# module_HC05.net
KiCad netlist of a schematic drawn in EAGLE
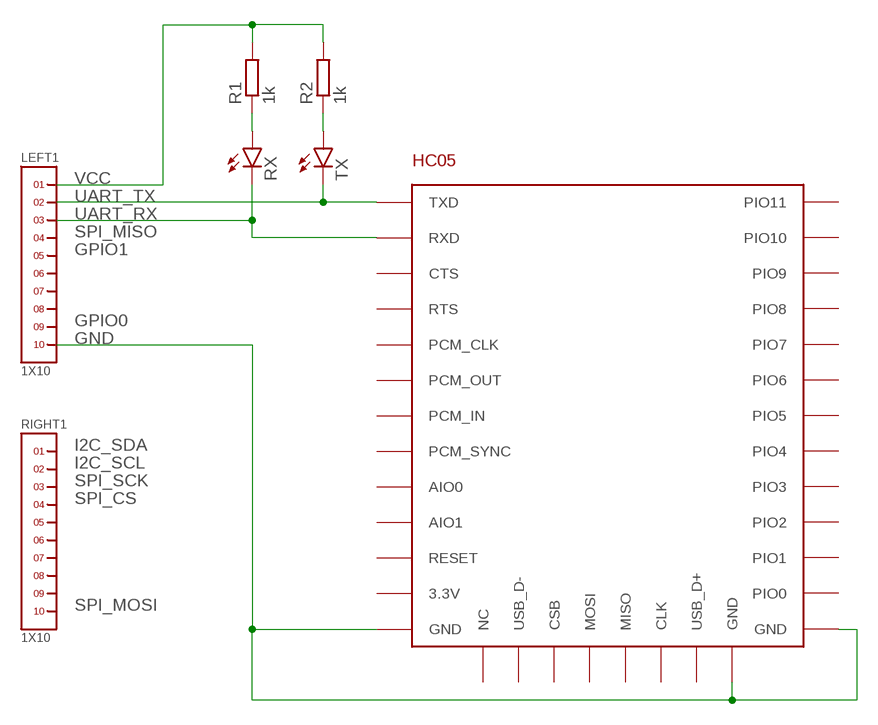
[diagram p0: schematic, sheet 1]

(export (version "E")
  (design (tool "Eeschema 10.0.6"))
  (components
    (comp (ref "LEFT1")
      (value "1X10")
      (footprint "eagle-import:1X10")
      (libsource (lib "eagle-import") (part "1X10"))
    )
    (comp (ref "R1")
      (value "1k")
      (footprint "eagle-import:R0603")
      (libsource (lib "eagle-import") (part "R-EU_R0603"))
    )
    (comp (ref "R2")
      (value "1k")
      (footprint "eagle-import:R0603")
      (libsource (lib "eagle-import") (part "R-EU_R0603"))
    )
    (comp (ref "RIGHT1")
      (value "1X10")
      (footprint "eagle-import:1X10")
      (libsource (lib "eagle-import") (part "1X10"))
    )
    (comp (ref "RX")
      (value "LEDCHIP-LED0603")
      (footprint "eagle-import:CHIP-LED0603")
      (libsource (lib "eagle-import") (part "LEDCHIP-LED0603"))
    )
    (comp (ref "TX")
      (value "LEDCHIP-LED0603")
      (footprint "eagle-import:CHIP-LED0603")
      (libsource (lib "eagle-import") (part "LEDCHIP-LED0603"))
    )
    (comp (ref "U$1")
      (value "HC05")
      (footprint "eagle-import:HC05")
      (libsource (lib "eagle-import") (part "HC05"))
    )
  )
  (nets
    (net (code "1") (name "Net-(LEFT1-Pad1)") (class "Default")
      (node (ref "LEFT1") (pin "1") (pinfunction "1_1") (pintype "bidirectional"))
      (node (ref "R1") (pin "2") (pinfunction "2_2") (pintype "passive"))
      (node (ref "R2") (pin "2") (pinfunction "2_2") (pintype "passive"))
    )
    (net (code "2") (name "Net-(LEFT1-Pad10)") (class "Default")
      (node (ref "LEFT1") (pin "10") (pinfunction "10_10") (pintype "bidirectional"))
      (node (ref "U$1") (pin "GND@1") (pinfunction "GND_GND@1") (pintype "bidirectional"))
      (node (ref "U$1") (pin "GND@2") (pinfunction "GND_GND@2") (pintype "bidirectional"))
      (node (ref "U$1") (pin "GND@3") (pinfunction "GND_GND@3") (pintype "bidirectional"))
    )
    (net (code "3") (name "Net-(R1-Pad1)") (class "Default")
      (node (ref "R1") (pin "1") (pinfunction "1_1") (pintype "passive"))
      (node (ref "RX") (pin "A") (pinfunction "A_A") (pintype "passive"))
    )
    (net (code "4") (name "Net-(R2-Pad1)") (class "Default")
      (node (ref "R2") (pin "1") (pinfunction "1_1") (pintype "passive"))
      (node (ref "TX") (pin "A") (pinfunction "A_A") (pintype "passive"))
    )
    (net (code "5") (name "Net-(U$1-RXD)") (class "Default")
      (node (ref "LEFT1") (pin "3") (pinfunction "3_3") (pintype "bidirectional"))
      (node (ref "RX") (pin "C") (pinfunction "C_C") (pintype "passive"))
      (node (ref "U$1") (pin "RX") (pinfunction "RXD_RX") (pintype "bidirectional"))
    )
    (net (code "6") (name "Net-(U$1-TXD)") (class "Default")
      (node (ref "LEFT1") (pin "2") (pinfunction "2_2") (pintype "bidirectional"))
      (node (ref "TX") (pin "C") (pinfunction "C_C") (pintype "passive"))
      (node (ref "U$1") (pin "TX") (pinfunction "TXD_TX") (pintype "bidirectional"))
    )
    (net (code "7") (name "unconnected-(LEFT1-Pad4)") (class "Default")
      (node (ref "LEFT1") (pin "4") (pinfunction "4_4") (pintype "bidirectional"))
    )
    (net (code "8") (name "unconnected-(LEFT1-Pad5)") (class "Default")
      (node (ref "LEFT1") (pin "5") (pinfunction "5_5") (pintype "bidirectional"))
    )
    (net (code "9") (name "unconnected-(LEFT1-Pad6)") (class "Default")
      (node (ref "LEFT1") (pin "6") (pinfunction "6_6") (pintype "bidirectional"))
    )
    (net (code "10") (name "unconnected-(LEFT1-Pad7)") (class "Default")
      (node (ref "LEFT1") (pin "7") (pinfunction "7_7") (pintype "bidirectional"))
    )
    (net (code "11") (name "unconnected-(LEFT1-Pad8)") (class "Default")
      (node (ref "LEFT1") (pin "8") (pinfunction "8_8") (pintype "bidirectional"))
    )
    (net (code "12") (name "unconnected-(LEFT1-Pad9)") (class "Default")
      (node (ref "LEFT1") (pin "9") (pinfunction "9_9") (pintype "bidirectional"))
    )
    (net (code "13") (name "unconnected-(RIGHT1-Pad1)") (class "Default")
      (node (ref "RIGHT1") (pin "1") (pinfunction "1_1") (pintype "bidirectional"))
    )
    (net (code "14") (name "unconnected-(RIGHT1-Pad2)") (class "Default")
      (node (ref "RIGHT1") (pin "2") (pinfunction "2_2") (pintype "bidirectional"))
    )
    (net (code "15") (name "unconnected-(RIGHT1-Pad3)") (class "Default")
      (node (ref "RIGHT1") (pin "3") (pinfunction "3_3") (pintype "bidirectional"))
    )
    (net (code "16") (name "unconnected-(RIGHT1-Pad4)") (class "Default")
      (node (ref "RIGHT1") (pin "4") (pinfunction "4_4") (pintype "bidirectional"))
    )
    (net (code "17") (name "unconnected-(RIGHT1-Pad5)") (class "Default")
      (node (ref "RIGHT1") (pin "5") (pinfunction "5_5") (pintype "bidirectional"))
    )
    (net (code "18") (name "unconnected-(RIGHT1-Pad6)") (class "Default")
      (node (ref "RIGHT1") (pin "6") (pinfunction "6_6") (pintype "bidirectional"))
    )
    (net (code "19") (name "unconnected-(RIGHT1-Pad7)") (class "Default")
      (node (ref "RIGHT1") (pin "7") (pinfunction "7_7") (pintype "bidirectional"))
    )
    (net (code "20") (name "unconnected-(RIGHT1-Pad8)") (class "Default")
      (node (ref "RIGHT1") (pin "8") (pinfunction "8_8") (pintype "bidirectional"))
    )
    (net (code "21") (name "unconnected-(RIGHT1-Pad9)") (class "Default")
      (node (ref "RIGHT1") (pin "9") (pinfunction "9_9") (pintype "bidirectional"))
    )
    (net (code "22") (name "unconnected-(RIGHT1-Pad10)") (class "Default")
      (node (ref "RIGHT1") (pin "10") (pinfunction "10_10") (pintype "bidirectional"))
    )
    (net (code "23") (name "unconnected-(U$1-Pad3.3V)") (class "Default")
      (node (ref "U$1") (pin "3.3V") (pinfunction "3.3V_3.3V") (pintype "bidirectional"))
    )
    (net (code "24") (name "unconnected-(U$1-PadAIO0)") (class "Default")
      (node (ref "U$1") (pin "AIO0") (pinfunction "AIO0_AIO0") (pintype "bidirectional"))
    )
    (net (code "25") (name "unconnected-(U$1-PadAIO1)") (class "Default")
      (node (ref "U$1") (pin "AIO1") (pinfunction "AIO1_AIO1") (pintype "bidirectional"))
    )
    (net (code "26") (name "unconnected-(U$1-PadCLK)") (class "Default")
      (node (ref "U$1") (pin "CLK") (pinfunction "CLK_CLK") (pintype "bidirectional"))
    )
    (net (code "27") (name "unconnected-(U$1-PadCSB)") (class "Default")
      (node (ref "U$1") (pin "CSB") (pinfunction "CSB_CSB") (pintype "bidirectional"))
    )
    (net (code "28") (name "unconnected-(U$1-PadCTS)") (class "Default")
      (node (ref "U$1") (pin "CTS") (pinfunction "CTS_CTS") (pintype "bidirectional"))
    )
    (net (code "29") (name "unconnected-(U$1-PadMISO)") (class "Default")
      (node (ref "U$1") (pin "MISO") (pinfunction "MISO_MISO") (pintype "bidirectional"))
    )
    (net (code "30") (name "unconnected-(U$1-PadMOSI)") (class "Default")
      (node (ref "U$1") (pin "MOSI") (pinfunction "MOSI_MOSI") (pintype "bidirectional"))
    )
    (net (code "31") (name "unconnected-(U$1-PadNC)") (class "Default")
      (node (ref "U$1") (pin "NC") (pinfunction "NC_NC") (pintype "bidirectional"))
    )
    (net (code "32") (name "unconnected-(U$1-PadPCM_CLK)") (class "Default")
      (node (ref "U$1") (pin "PCM_CLK") (pinfunction "PCM_CLK_PCM_CLK") (pintype "bidirectional"))
    )
    (net (code "33") (name "unconnected-(U$1-PadPCM_IN)") (class "Default")
      (node (ref "U$1") (pin "PCM_IN") (pinfunction "PCM_IN_PCM_IN") (pintype "bidirectional"))
    )
    (net (code "34") (name "unconnected-(U$1-PadPCM_OUT)") (class "Default")
      (node (ref "U$1") (pin "PCM_OUT") (pinfunction "PCM_OUT_PCM_OUT") (pintype "bidirectional"))
    )
    (net (code "35") (name "unconnected-(U$1-PadPCM_SYNC)") (class "Default")
      (node (ref "U$1") (pin "PCM_SYNC") (pinfunction "PCM_SYNC_PCM_SYNC") (pintype "bidirectional"))
    )
    (net (code "36") (name "unconnected-(U$1-PadPIO0)") (class "Default")
      (node (ref "U$1") (pin "PIO0") (pinfunction "PIO0_PIO0") (pintype "bidirectional"))
    )
    (net (code "37") (name "unconnected-(U$1-PadPIO1)") (class "Default")
      (node (ref "U$1") (pin "PIO1") (pinfunction "PIO1_PIO1") (pintype "bidirectional"))
    )
    (net (code "38") (name "unconnected-(U$1-PadPIO2)") (class "Default")
      (node (ref "U$1") (pin "PIO2") (pinfunction "PIO2_PIO2") (pintype "bidirectional"))
    )
    (net (code "39") (name "unconnected-(U$1-PadPIO3)") (class "Default")
      (node (ref "U$1") (pin "PIO3") (pinfunction "PIO3_PIO3") (pintype "bidirectional"))
    )
    (net (code "40") (name "unconnected-(U$1-PadPIO4)") (class "Default")
      (node (ref "U$1") (pin "PIO4") (pinfunction "PIO4_PIO4") (pintype "bidirectional"))
    )
    (net (code "41") (name "unconnected-(U$1-PadPIO5)") (class "Default")
      (node (ref "U$1") (pin "PIO5") (pinfunction "PIO5_PIO5") (pintype "bidirectional"))
    )
    (net (code "42") (name "unconnected-(U$1-PadPIO6)") (class "Default")
      (node (ref "U$1") (pin "PIO6") (pinfunction "PIO6_PIO6") (pintype "bidirectional"))
    )
    (net (code "43") (name "unconnected-(U$1-PadPIO7)") (class "Default")
      (node (ref "U$1") (pin "PIO7") (pinfunction "PIO7_PIO7") (pintype "bidirectional"))
    )
    (net (code "44") (name "unconnected-(U$1-PadPIO8)") (class "Default")
      (node (ref "U$1") (pin "PIO8") (pinfunction "PIO8_PIO8") (pintype "bidirectional"))
    )
    (net (code "45") (name "unconnected-(U$1-PadPIO9)") (class "Default")
      (node (ref "U$1") (pin "PIO9") (pinfunction "PIO9_PIO9") (pintype "bidirectional"))
    )
    (net (code "46") (name "unconnected-(U$1-PadPIO10)") (class "Default")
      (node (ref "U$1") (pin "PIO10") (pinfunction "PIO10_PIO10") (pintype "bidirectional"))
    )
    (net (code "47") (name "unconnected-(U$1-PadPIO11)") (class "Default")
      (node (ref "U$1") (pin "PIO11") (pinfunction "PIO11_PIO11") (pintype "bidirectional"))
    )
    (net (code "48") (name "unconnected-(U$1-PadRESET)") (class "Default")
      (node (ref "U$1") (pin "RESET") (pinfunction "RESET_RESET") (pintype "bidirectional"))
    )
    (net (code "49") (name "unconnected-(U$1-PadRTS)") (class "Default")
      (node (ref "U$1") (pin "RTS") (pinfunction "RTS_RTS") (pintype "bidirectional"))
    )
    (net (code "50") (name "unconnected-(U$1-PadUSB_D+)") (class "Default")
      (node (ref "U$1") (pin "USB_D+") (pinfunction "USB_D+_USB_D+") (pintype "bidirectional"))
    )
    (net (code "51") (name "unconnected-(U$1-PadUSB_D-)") (class "Default")
      (node (ref "U$1") (pin "USB_D-") (pinfunction "USB_D-_USB_D-") (pintype "bidirectional"))
    )
  )
)
